# W25_Chipset_-_1GBiT_SPI.net
KiCad netlist of a schematic drawn in Altium Designer
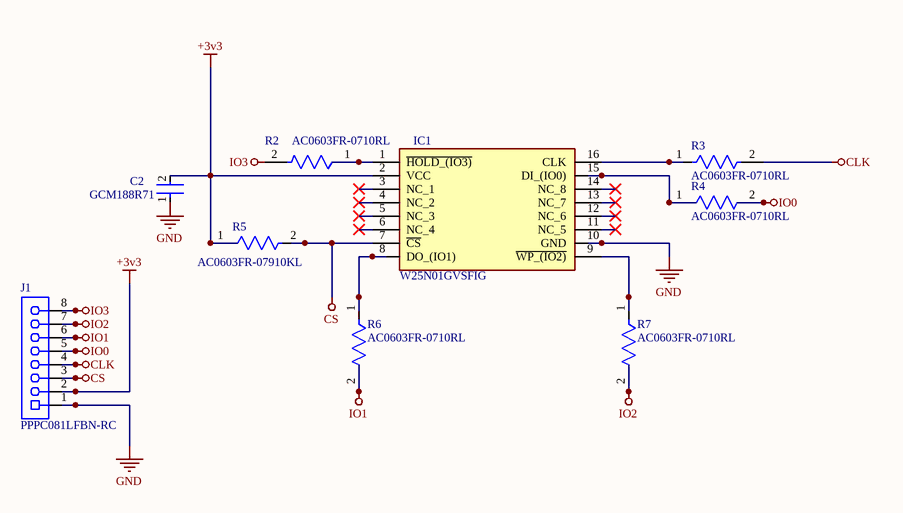
[diagram p0: W25 Chipset - 1GBiT SPI.SchDoc]

(export (version "E")
  (design (tool "Eeschema 10.0.6"))
  (components
    (comp (ref "C2")
      (value "GCM188R71")
      (footprint "FP-GCM188-0_1-IPC_B")
      (description "Ceramic Capacitor for Automotive 1uF  ±10% 16VDC X7R 0603 Paper T/R")
      (fields (field (name "VOLTAGE") "16V") (field (name "TOLERANCE") "10%"))
      (libsource (lib "Altium Content Vault") (part "02cd4be3c70576c341d710602a673aa"))
    )
    (comp (ref "IC1")
      (value "W25N01GVSFIG")
      (footprint "SamacSys:SOIC127P1032X264-16N")
      (description "Integrated Circuit")
      (fields (field (name "MOUSER PART NUMBER") "454-W25N01GVSFIG"))
      (libsource (lib "*") (part "W25N01GVSFIG"))
    )
    (comp (ref "J1")
      (value "PPPC081LFBN-RC")
      (footprint "SLIN-PPPC081LFBN-RC_V")
      (fields (field (name "MANUFACTURER") "Sullins"))
      (libsource (lib "Sean McDougall") (part "CN-1P-F-R8"))
    )
    (comp (ref "R2")
      (value "AC0603FR-0710RL")
      (footprint "FP-AC0603-MFG")
      (description "RES 10Ω 1.00% 0.1W 0603")
      (fields (field (name "TOLERANCE") "1%"))
      (libsource (lib "Altium Content Vault") (part "1029c3af85768c4190bb7ad29bc67b5"))
    )
    (comp (ref "R3")
      (value "AC0603FR-0710RL")
      (footprint "FP-AC0603-MFG")
      (description "RES 10Ω 1.00% 0.1W 0603")
      (fields (field (name "TOLERANCE") "1%"))
      (libsource (lib "Altium Content Vault") (part "1029c3af85768c4190bb7ad29bc67b5"))
    )
    (comp (ref "R4")
      (value "AC0603FR-0710RL")
      (footprint "FP-AC0603-MFG")
      (description "RES 10Ω 1.00% 0.1W 0603")
      (fields (field (name "TOLERANCE") "1%"))
      (libsource (lib "Altium Content Vault") (part "1029c3af85768c4190bb7ad29bc67b5"))
    )
    (comp (ref "R5")
      (value "AC0603FR-07910KL")
      (footprint "FP-AC0603-IPC_B")
      (description "RES 910KΩ 1.00% 0.1W 0603")
      (fields (field (name "TOLERANCE") "1%"))
      (libsource (lib "Altium Content Vault") (part "1029c3af85768c4190bb7ad29bc67b5"))
    )
    (comp (ref "R6")
      (value "AC0603FR-0710RL")
      (footprint "FP-AC0603-MFG")
      (description "RES 10Ω 1.00% 0.1W 0603")
      (fields (field (name "TOLERANCE") "1%"))
      (libsource (lib "Altium Content Vault") (part "1029c3af85768c4190bb7ad29bc67b5"))
    )
    (comp (ref "R7")
      (value "AC0603FR-0710RL")
      (footprint "FP-AC0603-MFG")
      (description "RES 10Ω 1.00% 0.1W 0603")
      (fields (field (name "TOLERANCE") "1%"))
      (libsource (lib "Altium Content Vault") (part "1029c3af85768c4190bb7ad29bc67b5"))
    )
  )
  (nets
    (net (code "1") (name "+3v3") (class "Default")
      (node (ref "C2") (pin "2") (pinfunction "2_2") (pintype "passive"))
      (node (ref "IC1") (pin "2") (pinfunction "VCC_2") (pintype "passive"))
      (node (ref "J1") (pin "2") (pinfunction "2_2") (pintype "passive"))
      (node (ref "R5") (pin "1") (pinfunction "1_1") (pintype "passive"))
    )
    (net (code "2") (name "CLK") (class "Default")
      (node (ref "J1") (pin "4") (pinfunction "4_4") (pintype "passive"))
      (node (ref "R3") (pin "2") (pinfunction "2_2") (pintype "passive"))
    )
    (net (code "3") (name "CS") (class "Default")
      (node (ref "IC1") (pin "7") (pinfunction "~{CS}_7") (pintype "passive"))
      (node (ref "J1") (pin "3") (pinfunction "3_3") (pintype "passive"))
      (node (ref "R5") (pin "2") (pinfunction "2_2") (pintype "passive"))
    )
    (net (code "4") (name "GND") (class "Default")
      (node (ref "C2") (pin "1") (pinfunction "1_1") (pintype "passive"))
      (node (ref "IC1") (pin "10") (pinfunction "GND_10") (pintype "passive"))
      (node (ref "J1") (pin "1") (pinfunction "1_1") (pintype "passive"))
    )
    (net (code "5") (name "IO0") (class "Default")
      (node (ref "J1") (pin "5") (pinfunction "5_5") (pintype "passive"))
      (node (ref "R4") (pin "2") (pinfunction "2_2") (pintype "passive"))
    )
    (net (code "6") (name "IO1") (class "Default")
      (node (ref "J1") (pin "6") (pinfunction "6_6") (pintype "passive"))
      (node (ref "R6") (pin "2") (pinfunction "2_2") (pintype "passive"))
    )
    (net (code "7") (name "IO2") (class "Default")
      (node (ref "J1") (pin "7") (pinfunction "7_7") (pintype "passive"))
      (node (ref "R7") (pin "2") (pinfunction "2_2") (pintype "passive"))
    )
    (net (code "8") (name "IO3") (class "Default")
      (node (ref "J1") (pin "8") (pinfunction "8_8") (pintype "passive"))
      (node (ref "R2") (pin "2") (pinfunction "2_2") (pintype "passive"))
    )
    (net (code "9") (name "Net-(IC1-CLK)") (class "Default")
      (node (ref "IC1") (pin "16") (pinfunction "CLK_16") (pintype "passive"))
      (node (ref "R3") (pin "1") (pinfunction "1_1") (pintype "passive"))
    )
    (net (code "10") (name "Net-(IC1-DI_(IO0))") (class "Default")
      (node (ref "IC1") (pin "15") (pinfunction "DI_(IO0)_15") (pintype "passive"))
      (node (ref "R4") (pin "1") (pinfunction "1_1") (pintype "passive"))
    )
    (net (code "11") (name "Net-(IC1-DO_(IO1))") (class "Default")
      (node (ref "IC1") (pin "8") (pinfunction "DO_(IO1)_8") (pintype "passive"))
      (node (ref "R6") (pin "1") (pinfunction "1_1") (pintype "passive"))
    )
    (net (code "12") (name "Net-(IC1-~{HOLD_(IO3)})") (class "Default")
      (node (ref "IC1") (pin "1") (pinfunction "~{HOLD_(IO3)}_1") (pintype "passive"))
      (node (ref "R2") (pin "1") (pinfunction "1_1") (pintype "passive"))
    )
    (net (code "13") (name "Net-(IC1-~{WP_(IO2)})") (class "Default")
      (node (ref "IC1") (pin "9") (pinfunction "~{WP_(IO2)}_9") (pintype "passive"))
      (node (ref "R7") (pin "1") (pinfunction "1_1") (pintype "passive"))
    )
    (net (code "14") (name "unconnected-(IC1-NC_1-Pad3)") (class "Default")
      (node (ref "IC1") (pin "3") (pinfunction "NC_1_3") (pintype "passive+no_connect"))
    )
    (net (code "15") (name "unconnected-(IC1-NC_2-Pad4)") (class "Default")
      (node (ref "IC1") (pin "4") (pinfunction "NC_2_4") (pintype "passive+no_connect"))
    )
    (net (code "16") (name "unconnected-(IC1-NC_3-Pad5)") (class "Default")
      (node (ref "IC1") (pin "5") (pinfunction "NC_3_5") (pintype "passive+no_connect"))
    )
    (net (code "17") (name "unconnected-(IC1-NC_4-Pad6)") (class "Default")
      (node (ref "IC1") (pin "6") (pinfunction "NC_4_6") (pintype "passive+no_connect"))
    )
    (net (code "18") (name "unconnected-(IC1-NC_5-Pad11)") (class "Default")
      (node (ref "IC1") (pin "11") (pinfunction "NC_5_11") (pintype "passive+no_connect"))
    )
    (net (code "19") (name "unconnected-(IC1-NC_6-Pad12)") (class "Default")
      (node (ref "IC1") (pin "12") (pinfunction "NC_6_12") (pintype "passive+no_connect"))
    )
    (net (code "20") (name "unconnected-(IC1-NC_7-Pad13)") (class "Default")
      (node (ref "IC1") (pin "13") (pinfunction "NC_7_13") (pintype "passive+no_connect"))
    )
    (net (code "21") (name "unconnected-(IC1-NC_8-Pad14)") (class "Default")
      (node (ref "IC1") (pin "14") (pinfunction "NC_8_14") (pintype "passive+no_connect"))
    )
  )
)
